# 03_ZYNQ_JTAG_BOOT.net
KiCad netlist of a schematic drawn in Altium Designer
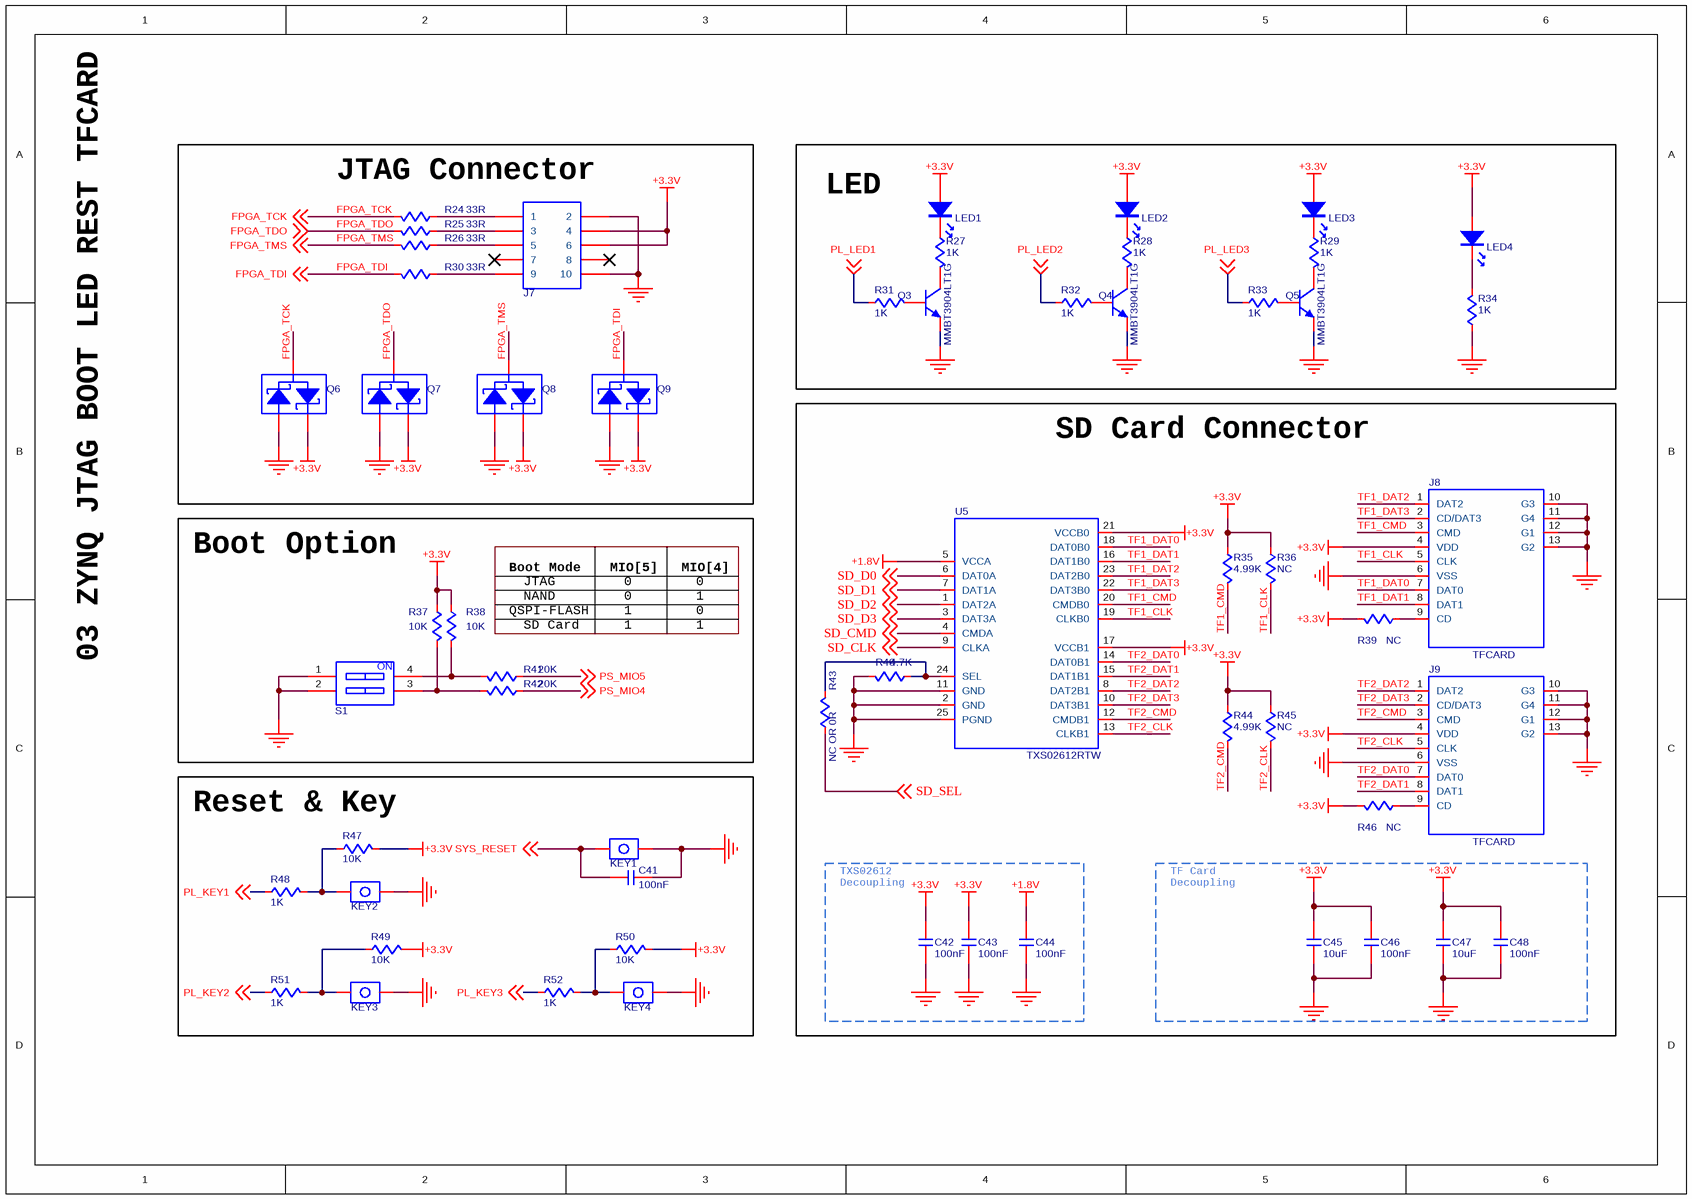
[diagram p0: 03_ZYNQ_JTAG_BOOT.SchDoc]

(export (version "E")
  (design (tool "Eeschema 10.0.6"))
  (components
    (comp (ref "C41")
      (value "100nF")
      (footprint "zynq:C0402")
      (fields (field (name "VOLTAGE") "25V") (field (name "Comment") "C-NOMO"))
      (libsource (lib "zynq") (part "C-NOMO"))
    )
    (comp (ref "C42")
      (value "100nF")
      (footprint "zynq:C0402")
      (fields (field (name "VOLTAGE") "25V") (field (name "Comment") "C-NOMO"))
      (libsource (lib "zynq") (part "C-NOMO"))
    )
    (comp (ref "C43")
      (value "100nF")
      (footprint "zynq:C0402")
      (fields (field (name "VOLTAGE") "25V") (field (name "Comment") "C-NOMO"))
      (libsource (lib "zynq") (part "C-NOMO"))
    )
    (comp (ref "C44")
      (value "100nF")
      (footprint "zynq:C0402")
      (fields (field (name "VOLTAGE") "25V") (field (name "Comment") "C-NOMO"))
      (libsource (lib "zynq") (part "C-NOMO"))
    )
    (comp (ref "C45")
      (value "10uF")
      (footprint "zynq:C0805")
      (fields (field (name "VOLTAGE") "25V") (field (name "Comment") "C-NOMO"))
      (libsource (lib "zynq") (part "C-NOMO"))
    )
    (comp (ref "C46")
      (value "100nF")
      (footprint "zynq:C0402")
      (fields (field (name "VOLTAGE") "25V") (field (name "Comment") "C-NOMO"))
      (libsource (lib "zynq") (part "C-NOMO"))
    )
    (comp (ref "C47")
      (value "10uF")
      (footprint "zynq:C0805")
      (fields (field (name "VOLTAGE") "25V") (field (name "Comment") "C-NOMO"))
      (libsource (lib "zynq") (part "C-NOMO"))
    )
    (comp (ref "C48")
      (value "100nF")
      (footprint "zynq:C0402")
      (fields (field (name "VOLTAGE") "25V") (field (name "Comment") "C-NOMO"))
      (libsource (lib "zynq") (part "C-NOMO"))
    )
    (comp (ref "J7") (value "HDR2X5") (footprint "zynq:HDR2X5-NJ") (libsource (lib "zynq") (part "HDR2X5")))
    (comp (ref "J8") (value "TFCARD") (footprint "zynq:TFCARD") (libsource (lib "zynq") (part "TFCARD")))
    (comp (ref "J9") (value "TFCARD") (footprint "zynq:TFCARD") (libsource (lib "zynq") (part "TFCARD")))
    (comp (ref "KEY1") (value "KEY") (footprint "zynq:KEY735SO") (libsource (lib "zynq") (part "KEY")))
    (comp (ref "KEY2") (value "KEY") (footprint "zynq:KEY735SO") (libsource (lib "zynq") (part "KEY")))
    (comp (ref "KEY3") (value "KEY") (footprint "zynq:KEY735SO") (libsource (lib "zynq") (part "KEY")))
    (comp (ref "KEY4") (value "KEY") (footprint "zynq:KEY735SO") (libsource (lib "zynq") (part "KEY")))
    (comp (ref "LED1") (value "LED") (footprint "zynq:LED0603") (libsource (lib "zynq") (part "LED")))
    (comp (ref "LED2") (value "LED") (footprint "zynq:LED0603") (libsource (lib "zynq") (part "LED")))
    (comp (ref "LED3") (value "LED") (footprint "zynq:LED0603") (libsource (lib "zynq") (part "LED")))
    (comp (ref "LED4") (value "LED") (footprint "zynq:LED0603") (libsource (lib "zynq") (part "LED")))
    (comp (ref "Q3") (value "MMBT3904LT1G") (footprint "zynq:SOT-23") (libsource (lib "zynq") (part "NPN")))
    (comp (ref "Q4") (value "MMBT3904LT1G") (footprint "zynq:SOT-23") (libsource (lib "zynq") (part "NPN")))
    (comp (ref "Q5") (value "MMBT3904LT1G") (footprint "zynq:SOT-23") (libsource (lib "zynq") (part "NPN")))
    (comp (ref "Q6") (value "BAT54S") (footprint "zynq:SOT-23") (libsource (lib "zynq") (part "BAT54S")))
    (comp (ref "Q7") (value "BAT54S") (footprint "zynq:SOT-23") (libsource (lib "zynq") (part "BAT54S")))
    (comp (ref "Q8") (value "BAT54S") (footprint "zynq:SOT-23") (libsource (lib "zynq") (part "BAT54S")))
    (comp (ref "Q9") (value "BAT54S") (footprint "zynq:SOT-23") (libsource (lib "zynq") (part "BAT54S")))
    (comp (ref "R24")
      (value "33R")
      (footprint "zynq:R0402")
      (fields (field (name "Comment") "R"))
      (libsource (lib "zynq") (part "R"))
    )
    (comp (ref "R25")
      (value "33R")
      (footprint "zynq:R0402")
      (fields (field (name "Comment") "R"))
      (libsource (lib "zynq") (part "R"))
    )
    (comp (ref "R26")
      (value "33R")
      (footprint "zynq:R0402")
      (fields (field (name "Comment") "R"))
      (libsource (lib "zynq") (part "R"))
    )
    (comp (ref "R27")
      (value "1K")
      (footprint "zynq:R0402")
      (fields (field (name "Comment") "R"))
      (libsource (lib "zynq") (part "R"))
    )
    (comp (ref "R28")
      (value "1K")
      (footprint "zynq:R0402")
      (fields (field (name "Comment") "R"))
      (libsource (lib "zynq") (part "R"))
    )
    (comp (ref "R29")
      (value "1K")
      (footprint "zynq:R0402")
      (fields (field (name "Comment") "R"))
      (libsource (lib "zynq") (part "R"))
    )
    (comp (ref "R30")
      (value "33R")
      (footprint "zynq:R0402")
      (fields (field (name "Comment") "R"))
      (libsource (lib "zynq") (part "R"))
    )
    (comp (ref "R31")
      (value "1K")
      (footprint "zynq:R0402")
      (fields (field (name "Comment") "R"))
      (libsource (lib "zynq") (part "R"))
    )
    (comp (ref "R32")
      (value "1K")
      (footprint "zynq:R0402")
      (fields (field (name "Comment") "R"))
      (libsource (lib "zynq") (part "R"))
    )
    (comp (ref "R33")
      (value "1K")
      (footprint "zynq:R0402")
      (fields (field (name "Comment") "R"))
      (libsource (lib "zynq") (part "R"))
    )
    (comp (ref "R34")
      (value "1K")
      (footprint "zynq:R0402")
      (fields (field (name "Comment") "R"))
      (libsource (lib "zynq") (part "R"))
    )
    (comp (ref "R35")
      (value "4.99K")
      (footprint "zynq:R0402")
      (fields (field (name "Comment") "R"))
      (libsource (lib "zynq") (part "R"))
    )
    (comp (ref "R36")
      (value "NC")
      (footprint "zynq:R0402")
      (fields (field (name "Comment") "R"))
      (libsource (lib "zynq") (part "R"))
    )
    (comp (ref "R37")
      (value "10K")
      (footprint "zynq:R0402")
      (fields (field (name "Comment") "R"))
      (libsource (lib "zynq") (part "R"))
    )
    (comp (ref "R38")
      (value "10K")
      (footprint "zynq:R0402")
      (fields (field (name "Comment") "R"))
      (libsource (lib "zynq") (part "R"))
    )
    (comp (ref "R39")
      (value "NC")
      (footprint "zynq:R0402")
      (fields (field (name "Comment") "R"))
      (libsource (lib "zynq") (part "R"))
    )
    (comp (ref "R40")
      (value "4.7K")
      (footprint "zynq:R0402")
      (fields (field (name "Comment") "R"))
      (libsource (lib "zynq") (part "R"))
    )
    (comp (ref "R41")
      (value "20K")
      (footprint "zynq:R0402")
      (fields (field (name "Comment") "R"))
      (libsource (lib "zynq") (part "R"))
    )
    (comp (ref "R42")
      (value "20K")
      (footprint "zynq:R0402")
      (fields (field (name "Comment") "R"))
      (libsource (lib "zynq") (part "R"))
    )
    (comp (ref "R43")
      (value "NC OR 0R")
      (footprint "zynq:R0402")
      (fields (field (name "Comment") "R"))
      (libsource (lib "zynq") (part "R"))
    )
    (comp (ref "R44")
      (value "4.99K")
      (footprint "zynq:R0402")
      (fields (field (name "Comment") "R"))
      (libsource (lib "zynq") (part "R"))
    )
    (comp (ref "R45")
      (value "NC")
      (footprint "zynq:R0402")
      (fields (field (name "Comment") "R"))
      (libsource (lib "zynq") (part "R"))
    )
    (comp (ref "R46")
      (value "NC")
      (footprint "zynq:R0402")
      (fields (field (name "Comment") "R"))
      (libsource (lib "zynq") (part "R"))
    )
    (comp (ref "R47")
      (value "10K")
      (footprint "zynq:R0402")
      (fields (field (name "Comment") "R"))
      (libsource (lib "zynq") (part "R"))
    )
    (comp (ref "R48")
      (value "1K")
      (footprint "zynq:R0402")
      (fields (field (name "Comment") "R"))
      (libsource (lib "zynq") (part "R"))
    )
    (comp (ref "R49")
      (value "10K")
      (footprint "zynq:R0402")
      (fields (field (name "Comment") "R"))
      (libsource (lib "zynq") (part "R"))
    )
    (comp (ref "R50")
      (value "10K")
      (footprint "zynq:R0402")
      (fields (field (name "Comment") "R"))
      (libsource (lib "zynq") (part "R"))
    )
    (comp (ref "R51")
      (value "1K")
      (footprint "zynq:R0402")
      (fields (field (name "Comment") "R"))
      (libsource (lib "zynq") (part "R"))
    )
    (comp (ref "R52")
      (value "1K")
      (footprint "zynq:R0402")
      (fields (field (name "Comment") "R"))
      (libsource (lib "zynq") (part "R"))
    )
    (comp (ref "S1") (value "Switch") (footprint "zynq:DHN02VTR") (libsource (lib "zynq") (part "SW-2")))
    (comp (ref "U5")
      (value "TXS02612RTW")
      (footprint "zynq:TXS02612TWR")
      (libsource (lib "zynq") (part "TXS02612RTW"))
    )
  )
  (nets
    (net (code "1") (name "+1.8V") (class "Default")
      (node (ref "C44") (pin "2") (pinfunction "2_2") (pintype "passive"))
      (node (ref "U5") (pin "5") (pinfunction "VCCA_5") (pintype "passive"))
    )
    (net (code "2") (name "+3.3V") (class "Default")
      (node (ref "C42") (pin "2") (pinfunction "2_2") (pintype "passive"))
      (node (ref "C43") (pin "2") (pinfunction "2_2") (pintype "passive"))
      (node (ref "C45") (pin "2") (pinfunction "2_2") (pintype "passive"))
      (node (ref "C46") (pin "2") (pinfunction "2_2") (pintype "passive"))
      (node (ref "C47") (pin "2") (pinfunction "2_2") (pintype "passive"))
      (node (ref "C48") (pin "2") (pinfunction "2_2") (pintype "passive"))
      (node (ref "J7") (pin "4") (pinfunction "4_4") (pintype "passive"))
      (node (ref "J7") (pin "6") (pinfunction "6_6") (pintype "passive"))
      (node (ref "J8") (pin "4") (pinfunction "VDD_4") (pintype "passive"))
      (node (ref "J9") (pin "4") (pinfunction "VDD_4") (pintype "passive"))
      (node (ref "LED1") (pin "2") (pinfunction "2_2") (pintype "passive"))
      (node (ref "LED2") (pin "2") (pinfunction "2_2") (pintype "passive"))
      (node (ref "LED3") (pin "2") (pinfunction "2_2") (pintype "passive"))
      (node (ref "LED4") (pin "2") (pinfunction "2_2") (pintype "passive"))
      (node (ref "Q6") (pin "2") (pinfunction "2_2") (pintype "passive"))
      (node (ref "Q7") (pin "2") (pinfunction "2_2") (pintype "passive"))
      (node (ref "Q8") (pin "2") (pinfunction "2_2") (pintype "passive"))
      (node (ref "Q9") (pin "2") (pinfunction "2_2") (pintype "passive"))
      (node (ref "R35") (pin "2") (pinfunction "2_2") (pintype "passive"))
      (node (ref "R36") (pin "2") (pinfunction "2_2") (pintype "passive"))
      (node (ref "R37") (pin "2") (pinfunction "2_2") (pintype "passive"))
      (node (ref "R38") (pin "2") (pinfunction "2_2") (pintype "passive"))
      (node (ref "R39") (pin "1") (pinfunction "1_1") (pintype "passive"))
      (node (ref "R44") (pin "2") (pinfunction "2_2") (pintype "passive"))
      (node (ref "R45") (pin "2") (pinfunction "2_2") (pintype "passive"))
      (node (ref "R46") (pin "1") (pinfunction "1_1") (pintype "passive"))
      (node (ref "R47") (pin "1") (pinfunction "1_1") (pintype "passive"))
      (node (ref "R49") (pin "1") (pinfunction "1_1") (pintype "passive"))
      (node (ref "R50") (pin "1") (pinfunction "1_1") (pintype "passive"))
      (node (ref "U5") (pin "17") (pinfunction "VCCB1_17") (pintype "passive"))
      (node (ref "U5") (pin "21") (pinfunction "VCCB0_21") (pintype "passive"))
    )
    (net (code "3") (name "/TF1_CLK") (class "Default")
      (node (ref "J8") (pin "5") (pinfunction "CLK_5") (pintype "passive"))
      (node (ref "R36") (pin "1") (pinfunction "1_1") (pintype "passive"))
      (node (ref "U5") (pin "19") (pinfunction "CLKB0_19") (pintype "passive"))
    )
    (net (code "4") (name "/TF1_CMD") (class "Default")
      (node (ref "J8") (pin "3") (pinfunction "CMD_3") (pintype "passive"))
      (node (ref "R35") (pin "1") (pinfunction "1_1") (pintype "passive"))
      (node (ref "U5") (pin "20") (pinfunction "CMDB0_20") (pintype "passive"))
    )
    (net (code "5") (name "/TF1_DAT0") (class "Default")
      (node (ref "J8") (pin "7") (pinfunction "DAT0_7") (pintype "passive"))
      (node (ref "U5") (pin "18") (pinfunction "DAT0B0_18") (pintype "passive"))
    )
    (net (code "6") (name "/TF1_DAT1") (class "Default")
      (node (ref "J8") (pin "8") (pinfunction "DAT1_8") (pintype "passive"))
      (node (ref "U5") (pin "16") (pinfunction "DAT1B0_16") (pintype "passive"))
    )
    (net (code "7") (name "/TF1_DAT2") (class "Default")
      (node (ref "J8") (pin "1") (pinfunction "DAT2_1") (pintype "passive"))
      (node (ref "U5") (pin "23") (pinfunction "DAT2B0_23") (pintype "passive"))
    )
    (net (code "8") (name "/TF1_DAT3") (class "Default")
      (node (ref "J8") (pin "2") (pinfunction "CD/DAT3_2") (pintype "passive"))
      (node (ref "U5") (pin "22") (pinfunction "DAT3B0_22") (pintype "passive"))
    )
    (net (code "9") (name "/TF2_CLK") (class "Default")
      (node (ref "J9") (pin "5") (pinfunction "CLK_5") (pintype "passive"))
      (node (ref "R45") (pin "1") (pinfunction "1_1") (pintype "passive"))
      (node (ref "U5") (pin "13") (pinfunction "CLKB1_13") (pintype "passive"))
    )
    (net (code "10") (name "/TF2_CMD") (class "Default")
      (node (ref "J9") (pin "3") (pinfunction "CMD_3") (pintype "passive"))
      (node (ref "R44") (pin "1") (pinfunction "1_1") (pintype "passive"))
      (node (ref "U5") (pin "12") (pinfunction "CMDB1_12") (pintype "passive"))
    )
    (net (code "11") (name "/TF2_DAT0") (class "Default")
      (node (ref "J9") (pin "7") (pinfunction "DAT0_7") (pintype "passive"))
      (node (ref "U5") (pin "14") (pinfunction "DAT0B1_14") (pintype "passive"))
    )
    (net (code "12") (name "/TF2_DAT1") (class "Default")
      (node (ref "J9") (pin "8") (pinfunction "DAT1_8") (pintype "passive"))
      (node (ref "U5") (pin "15") (pinfunction "DAT1B1_15") (pintype "passive"))
    )
    (net (code "13") (name "/TF2_DAT2") (class "Default")
      (node (ref "J9") (pin "1") (pinfunction "DAT2_1") (pintype "passive"))
      (node (ref "U5") (pin "8") (pinfunction "DAT2B1_8") (pintype "passive"))
    )
    (net (code "14") (name "/TF2_DAT3") (class "Default")
      (node (ref "J9") (pin "2") (pinfunction "CD/DAT3_2") (pintype "passive"))
      (node (ref "U5") (pin "10") (pinfunction "DAT3B1_10") (pintype "passive"))
    )
    (net (code "15") (name "FPGA_TCK") (class "Default")
      (node (ref "Q6") (pin "3") (pinfunction "3_3") (pintype "passive"))
      (node (ref "R24") (pin "1") (pinfunction "1_1") (pintype "passive"))
    )
    (net (code "16") (name "FPGA_TDI") (class "Default")
      (node (ref "Q9") (pin "3") (pinfunction "3_3") (pintype "passive"))
      (node (ref "R30") (pin "1") (pinfunction "1_1") (pintype "passive"))
    )
    (net (code "17") (name "FPGA_TDO") (class "Default")
      (node (ref "Q7") (pin "3") (pinfunction "3_3") (pintype "passive"))
      (node (ref "R25") (pin "1") (pinfunction "1_1") (pintype "passive"))
    )
    (net (code "18") (name "FPGA_TMS") (class "Default")
      (node (ref "Q8") (pin "3") (pinfunction "3_3") (pintype "passive"))
      (node (ref "R26") (pin "1") (pinfunction "1_1") (pintype "passive"))
    )
    (net (code "19") (name "GND") (class "Default")
      (node (ref "C41") (pin "2") (pinfunction "2_2") (pintype "passive"))
      (node (ref "C42") (pin "1") (pinfunction "1_1") (pintype "passive"))
      (node (ref "C43") (pin "1") (pinfunction "1_1") (pintype "passive"))
      (node (ref "C44") (pin "1") (pinfunction "1_1") (pintype "passive"))
      (node (ref "C45") (pin "1") (pinfunction "1_1") (pintype "passive"))
      (node (ref "C46") (pin "1") (pinfunction "1_1") (pintype "passive"))
      (node (ref "C47") (pin "1") (pinfunction "1_1") (pintype "passive"))
      (node (ref "C48") (pin "1") (pinfunction "1_1") (pintype "passive"))
      (node (ref "J7") (pin "10") (pinfunction "10_10") (pintype "passive"))
      (node (ref "J7") (pin "2") (pinfunction "2_2") (pintype "passive"))
      (node (ref "J8") (pin "10") (pinfunction "G3_10") (pintype "passive"))
      (node (ref "J8") (pin "11") (pinfunction "G4_11") (pintype "passive"))
      (node (ref "J8") (pin "12") (pinfunction "G1_12") (pintype "passive"))
      (node (ref "J8") (pin "13") (pinfunction "G2_13") (pintype "passive"))
      (node (ref "J8") (pin "6") (pinfunction "VSS_6") (pintype "passive"))
      (node (ref "J9") (pin "10") (pinfunction "G3_10") (pintype "passive"))
      (node (ref "J9") (pin "11") (pinfunction "G4_11") (pintype "passive"))
      (node (ref "J9") (pin "12") (pinfunction "G1_12") (pintype "passive"))
      (node (ref "J9") (pin "13") (pinfunction "G2_13") (pintype "passive"))
      (node (ref "J9") (pin "6") (pinfunction "VSS_6") (pintype "passive"))
      (node (ref "KEY1") (pin "2") (pinfunction "2_2") (pintype "passive"))
      (node (ref "KEY2") (pin "2") (pinfunction "2_2") (pintype "passive"))
      (node (ref "KEY3") (pin "2") (pinfunction "2_2") (pintype "passive"))
      (node (ref "KEY4") (pin "2") (pinfunction "2_2") (pintype "passive"))
      (node (ref "Q3") (pin "2") (pinfunction "E_2") (pintype "passive"))
      (node (ref "Q4") (pin "2") (pinfunction "E_2") (pintype "passive"))
      (node (ref "Q5") (pin "2") (pinfunction "E_2") (pintype "passive"))
      (node (ref "Q6") (pin "1") (pinfunction "1_1") (pintype "passive"))
      (node (ref "Q7") (pin "1") (pinfunction "1_1") (pintype "passive"))
      (node (ref "Q8") (pin "1") (pinfunction "1_1") (pintype "passive"))
      (node (ref "Q9") (pin "1") (pinfunction "1_1") (pintype "passive"))
      (node (ref "R34") (pin "2") (pinfunction "2_2") (pintype "passive"))
      (node (ref "R40") (pin "1") (pinfunction "1_1") (pintype "passive"))
      (node (ref "S1") (pin "1") (pinfunction "A1_1") (pintype "passive"))
      (node (ref "S1") (pin "2") (pinfunction "A2_2") (pintype "passive"))
      (node (ref "U5") (pin "11") (pinfunction "GND_11") (pintype "passive"))
      (node (ref "U5") (pin "2") (pinfunction "GND_2") (pintype "passive"))
      (node (ref "U5") (pin "25") (pinfunction "PGND_25") (pintype "passive"))
    )
    (net (code "20") (name "Net-(J7-Pad1)") (class "Default")
      (node (ref "J7") (pin "1") (pinfunction "1_1") (pintype "passive"))
      (node (ref "R24") (pin "2") (pinfunction "2_2") (pintype "passive"))
    )
    (net (code "21") (name "Net-(J7-Pad3)") (class "Default")
      (node (ref "J7") (pin "3") (pinfunction "3_3") (pintype "passive"))
      (node (ref "R25") (pin "2") (pinfunction "2_2") (pintype "passive"))
    )
    (net (code "22") (name "Net-(J7-Pad5)") (class "Default")
      (node (ref "J7") (pin "5") (pinfunction "5_5") (pintype "passive"))
      (node (ref "R26") (pin "2") (pinfunction "2_2") (pintype "passive"))
    )
    (net (code "23") (name "Net-(J7-Pad9)") (class "Default")
      (node (ref "J7") (pin "9") (pinfunction "9_9") (pintype "passive"))
      (node (ref "R30") (pin "2") (pinfunction "2_2") (pintype "passive"))
    )
    (net (code "24") (name "Net-(J8-CD)") (class "Default")
      (node (ref "J8") (pin "9") (pinfunction "CD_9") (pintype "passive"))
      (node (ref "R39") (pin "2") (pinfunction "2_2") (pintype "passive"))
    )
    (net (code "25") (name "Net-(J9-CD)") (class "Default")
      (node (ref "J9") (pin "9") (pinfunction "CD_9") (pintype "passive"))
      (node (ref "R46") (pin "2") (pinfunction "2_2") (pintype "passive"))
    )
    (net (code "26") (name "Net-(KEY2-Pad1)") (class "Default")
      (node (ref "KEY2") (pin "1") (pinfunction "1_1") (pintype "passive"))
      (node (ref "R47") (pin "2") (pinfunction "2_2") (pintype "passive"))
      (node (ref "R48") (pin "1") (pinfunction "1_1") (pintype "passive"))
    )
    (net (code "27") (name "Net-(KEY3-Pad1)") (class "Default")
      (node (ref "KEY3") (pin "1") (pinfunction "1_1") (pintype "passive"))
      (node (ref "R49") (pin "2") (pinfunction "2_2") (pintype "passive"))
      (node (ref "R51") (pin "1") (pinfunction "1_1") (pintype "passive"))
    )
    (net (code "28") (name "Net-(KEY4-Pad1)") (class "Default")
      (node (ref "KEY4") (pin "1") (pinfunction "1_1") (pintype "passive"))
      (node (ref "R50") (pin "2") (pinfunction "2_2") (pintype "passive"))
      (node (ref "R52") (pin "1") (pinfunction "1_1") (pintype "passive"))
    )
    (net (code "29") (name "Net-(LED1-Pad1)") (class "Default")
      (node (ref "LED1") (pin "1") (pinfunction "1_1") (pintype "passive"))
      (node (ref "R27") (pin "2") (pinfunction "2_2") (pintype "passive"))
    )
    (net (code "30") (name "Net-(LED2-Pad1)") (class "Default")
      (node (ref "LED2") (pin "1") (pinfunction "1_1") (pintype "passive"))
      (node (ref "R28") (pin "2") (pinfunction "2_2") (pintype "passive"))
    )
    (net (code "31") (name "Net-(LED3-Pad1)") (class "Default")
      (node (ref "LED3") (pin "1") (pinfunction "1_1") (pintype "passive"))
      (node (ref "R29") (pin "2") (pinfunction "2_2") (pintype "passive"))
    )
    (net (code "32") (name "Net-(LED4-Pad1)") (class "Default")
      (node (ref "LED4") (pin "1") (pinfunction "1_1") (pintype "passive"))
      (node (ref "R34") (pin "1") (pinfunction "1_1") (pintype "passive"))
    )
    (net (code "33") (name "Net-(Q3-B)") (class "Default")
      (node (ref "Q3") (pin "1") (pinfunction "B_1") (pintype "passive"))
      (node (ref "R31") (pin "1") (pinfunction "1_1") (pintype "passive"))
    )
    (net (code "34") (name "Net-(Q3-C)") (class "Default")
      (node (ref "Q3") (pin "3") (pinfunction "C_3") (pintype "passive"))
      (node (ref "R27") (pin "1") (pinfunction "1_1") (pintype "passive"))
    )
    (net (code "35") (name "Net-(Q4-B)") (class "Default")
      (node (ref "Q4") (pin "1") (pinfunction "B_1") (pintype "passive"))
      (node (ref "R32") (pin "1") (pinfunction "1_1") (pintype "passive"))
    )
    (net (code "36") (name "Net-(Q4-C)") (class "Default")
      (node (ref "Q4") (pin "3") (pinfunction "C_3") (pintype "passive"))
      (node (ref "R28") (pin "1") (pinfunction "1_1") (pintype "passive"))
    )
    (net (code "37") (name "Net-(Q5-B)") (class "Default")
      (node (ref "Q5") (pin "1") (pinfunction "B_1") (pintype "passive"))
      (node (ref "R33") (pin "1") (pinfunction "1_1") (pintype "passive"))
    )
    (net (code "38") (name "Net-(Q5-C)") (class "Default")
      (node (ref "Q5") (pin "3") (pinfunction "C_3") (pintype "passive"))
      (node (ref "R29") (pin "1") (pinfunction "1_1") (pintype "passive"))
    )
    (net (code "39") (name "Net-(S1-B1)") (class "Default")
      (node (ref "R38") (pin "1") (pinfunction "1_1") (pintype "passive"))
      (node (ref "R41") (pin "1") (pinfunction "1_1") (pintype "passive"))
      (node (ref "S1") (pin "4") (pinfunction "B1_4") (pintype "passive"))
    )
    (net (code "40") (name "Net-(S1-B2)") (class "Default")
      (node (ref "R37") (pin "1") (pinfunction "1_1") (pintype "passive"))
      (node (ref "R42") (pin "1") (pinfunction "1_1") (pintype "passive"))
      (node (ref "S1") (pin "3") (pinfunction "B2_3") (pintype "passive"))
    )
    (net (code "41") (name "Net-(U5-SEL)") (class "Default")
      (node (ref "R40") (pin "2") (pinfunction "2_2") (pintype "passive"))
      (node (ref "R43") (pin "1") (pinfunction "1_1") (pintype "passive"))
      (node (ref "U5") (pin "24") (pinfunction "SEL_24") (pintype "passive"))
    )
    (net (code "42") (name "PL_KEY1") (class "Default")
      (node (ref "R48") (pin "2") (pinfunction "2_2") (pintype "passive"))
    )
    (net (code "43") (name "PL_KEY2") (class "Default")
      (node (ref "R51") (pin "2") (pinfunction "2_2") (pintype "passive"))
    )
    (net (code "44") (name "PL_KEY3") (class "Default")
      (node (ref "R52") (pin "2") (pinfunction "2_2") (pintype "passive"))
    )
    (net (code "45") (name "PL_LED1") (class "Default")
      (node (ref "R31") (pin "2") (pinfunction "2_2") (pintype "passive"))
    )
    (net (code "46") (name "PL_LED2") (class "Default")
      (node (ref "R32") (pin "2") (pinfunction "2_2") (pintype "passive"))
    )
    (net (code "47") (name "PL_LED3") (class "Default")
      (node (ref "R33") (pin "2") (pinfunction "2_2") (pintype "passive"))
    )
    (net (code "48") (name "PS_MIO4") (class "Default")
      (node (ref "R42") (pin "2") (pinfunction "2_2") (pintype "passive"))
    )
    (net (code "49") (name "PS_MIO5") (class "Default")
      (node (ref "R41") (pin "2") (pinfunction "2_2") (pintype "passive"))
    )
    (net (code "50") (name "SD_CLK") (class "Default")
      (node (ref "U5") (pin "9") (pinfunction "CLKA_9") (pintype "passive"))
    )
    (net (code "51") (name "SD_CMD") (class "Default")
      (node (ref "U5") (pin "4") (pinfunction "CMDA_4") (pintype "passive"))
    )
    (net (code "52") (name "SD_D0") (class "Default")
      (node (ref "U5") (pin "6") (pinfunction "DAT0A_6") (pintype "passive"))
    )
    (net (code "53") (name "SD_D1") (class "Default")
      (node (ref "U5") (pin "7") (pinfunction "DAT1A_7") (pintype "passive"))
    )
    (net (code "54") (name "SD_D2") (class "Default")
      (node (ref "U5") (pin "1") (pinfunction "DAT2A_1") (pintype "passive"))
    )
    (net (code "55") (name "SD_D3") (class "Default")
      (node (ref "U5") (pin "3") (pinfunction "DAT3A_3") (pintype "passive"))
    )
    (net (code "56") (name "SD_SEL") (class "Default")
      (node (ref "R43") (pin "2") (pinfunction "2_2") (pintype "passive"))
    )
    (net (code "57") (name "SYS_RESET") (class "Default")
      (node (ref "C41") (pin "1") (pinfunction "1_1") (pintype "passive"))
      (node (ref "KEY1") (pin "1") (pinfunction "1_1") (pintype "passive"))
    )
    (net (code "58") (name "unconnected-(J7-Pad7)") (class "Default")
      (node (ref "J7") (pin "7") (pinfunction "7_7") (pintype "passive+no_connect"))
    )
    (net (code "59") (name "unconnected-(J7-Pad8)") (class "Default")
      (node (ref "J7") (pin "8") (pinfunction "8_8") (pintype "passive+no_connect"))
    )
  )
)
